# OpenPLCv0_2_0_Power.net
KiCad netlist of a schematic drawn in Altium Designer
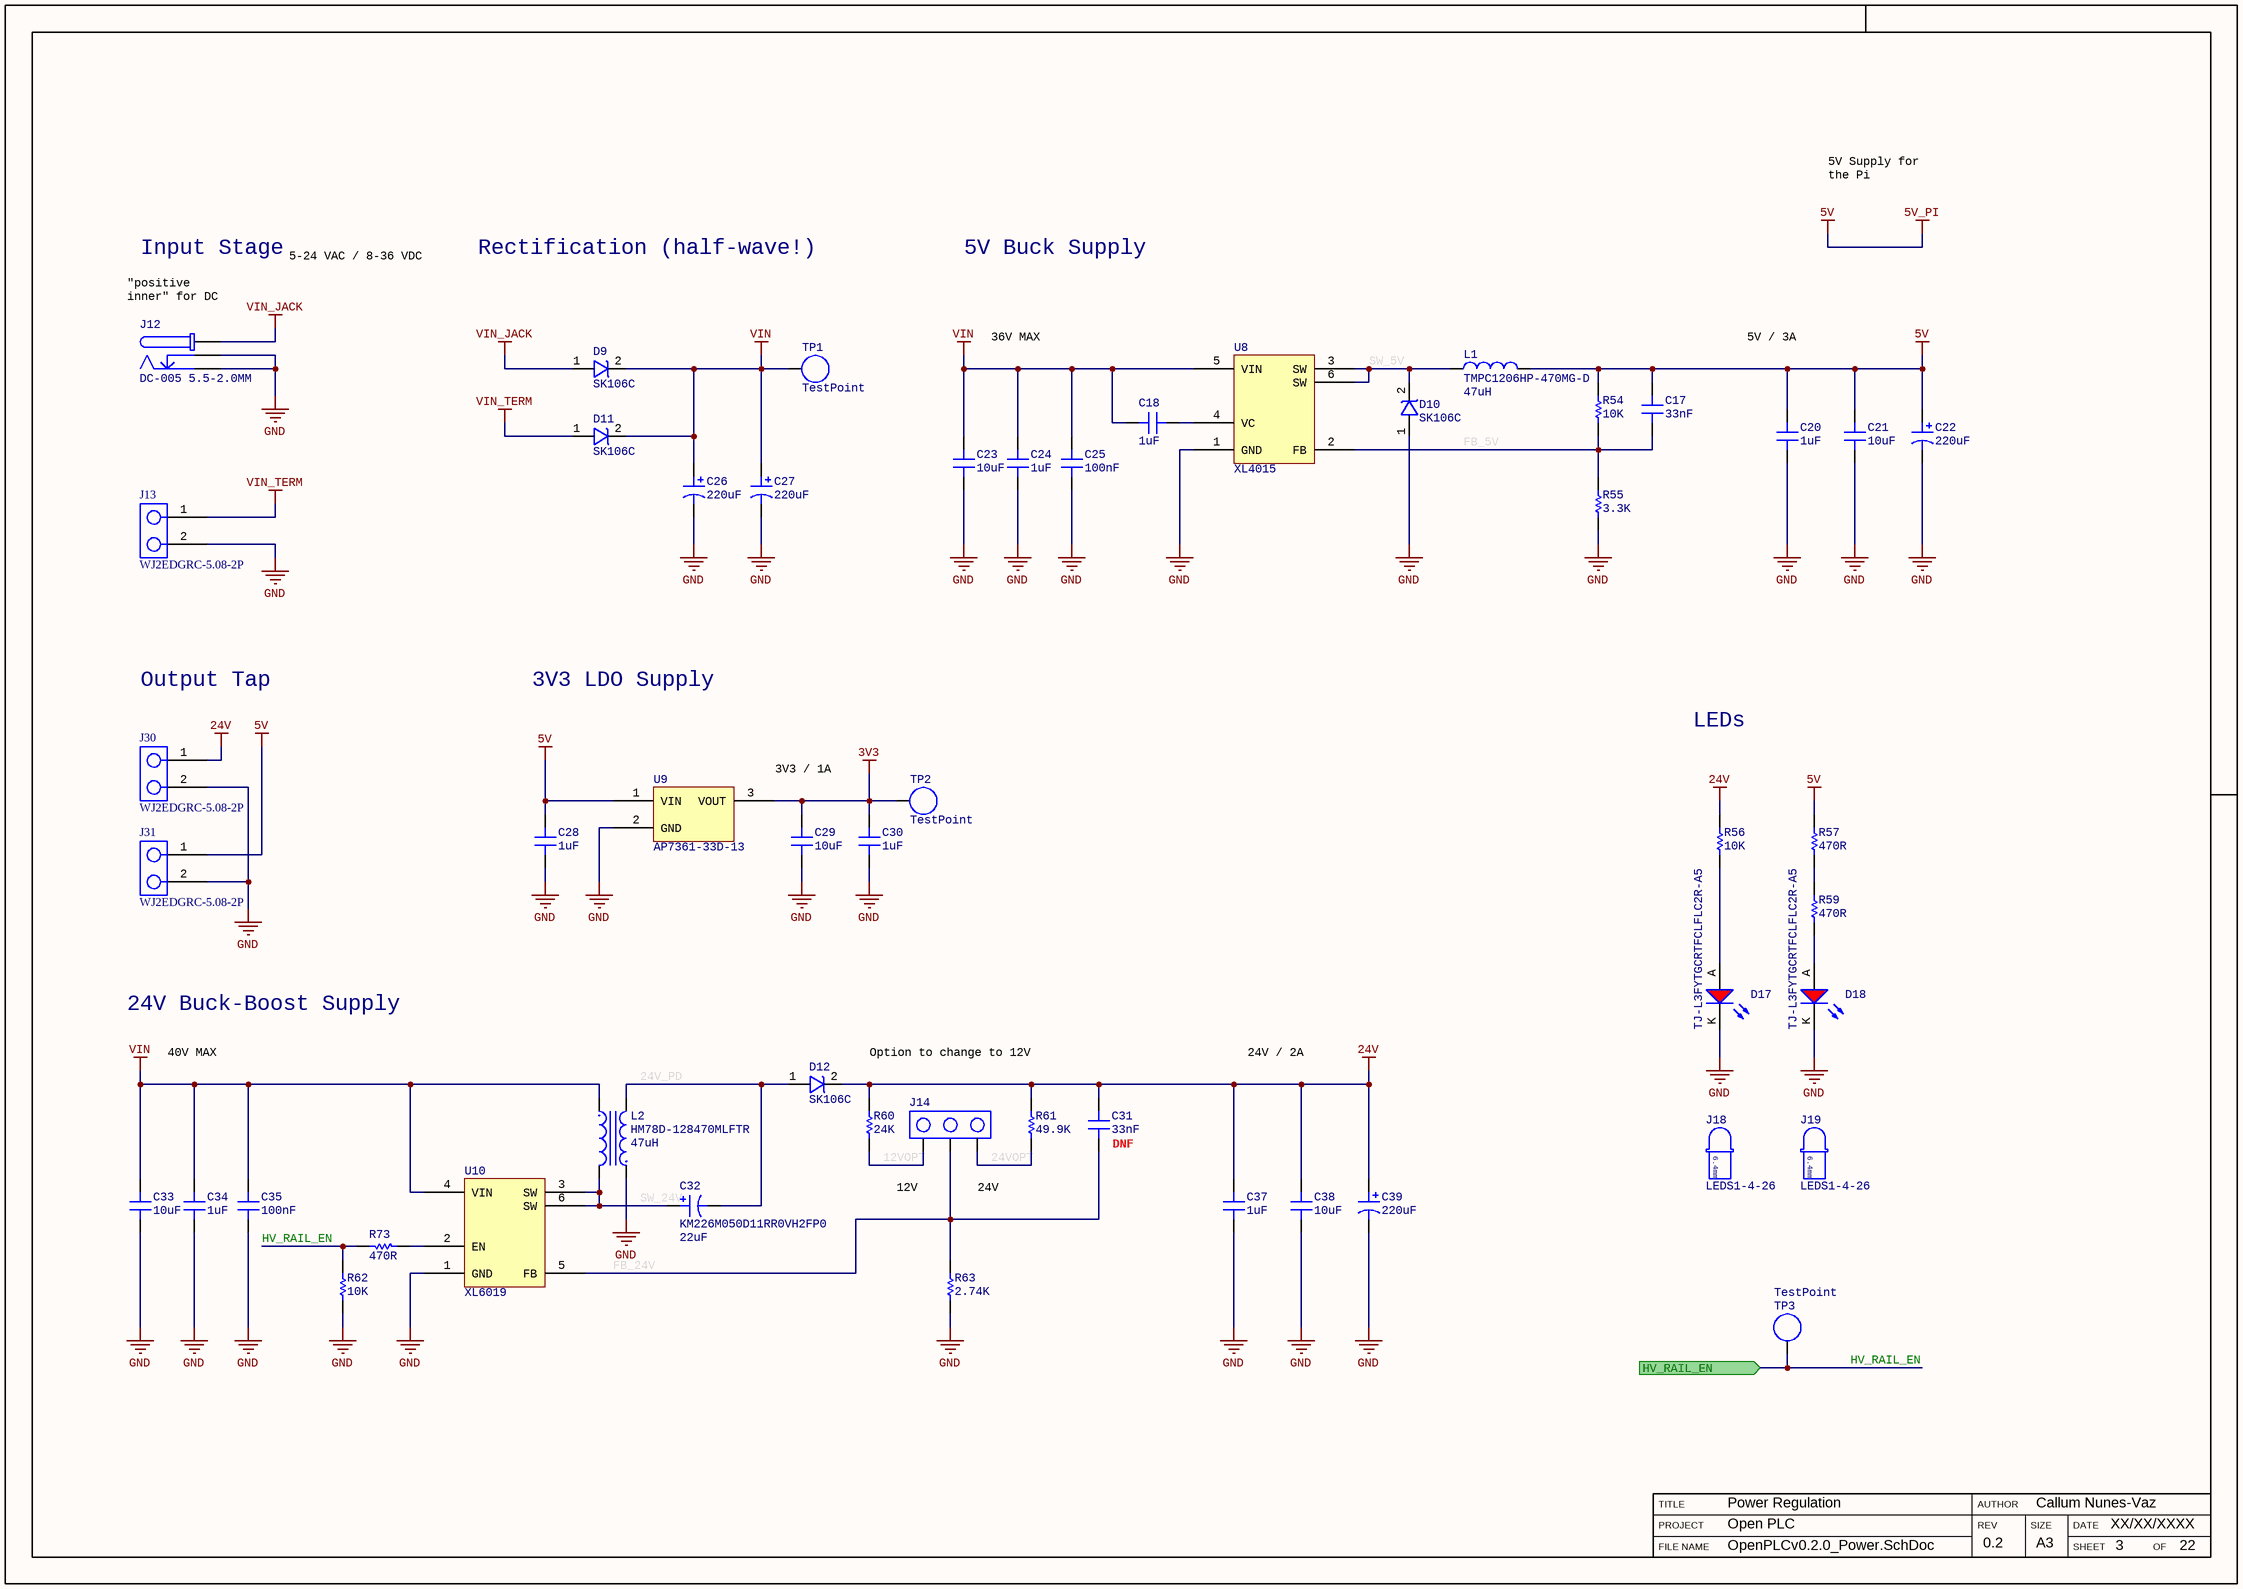
[diagram p0: OpenPLCv0.2.0_Power.SchDoc]

(export (version "E")
  (design (tool "Eeschema 10.0.6"))
  (components
    (comp (ref "C17")
      (value "CC0402KRX7R9BB333")
      (footprint "SMD_CAP_0402(1005)_N")
      (description "33nF ±10% 50V X7R 0402 Multilayer Ceramic Capacitors MLCC - SMD/SMT RoHS")
      (fields (field (name "TOLERANCE") "10%") (field (name "CAPACITANCE") "33nF"))
      (libsource (lib "BrauV2_Capacitor") (part "33nF 0402 50V 10%"))
    )
    (comp (ref "C18")
      (value "CC0603KRX5R9BB105")
      (footprint "SMD_CAP_0603(0201)_N")
      (description "1uF ±10% 50V X5R 0603 Multilayer Ceramic Capacitors MLCC - SMD/SMT RoHS")
      (fields (field (name "TOLERANCE") "10%") (field (name "CAPACITANCE") "1uF"))
      (libsource (lib "BrauV2_Capacitor") (part "1uF 0603 50V 10%"))
    )
    (comp (ref "C20")
      (value "CC0603KRX5R9BB105")
      (footprint "SMD_CAP_0603(0201)_N")
      (description "1uF ±10% 50V X5R 0603 Multilayer Ceramic Capacitors MLCC - SMD/SMT RoHS")
      (fields (field (name "TOLERANCE") "10%") (field (name "CAPACITANCE") "1uF"))
      (libsource (lib "BrauV2_Capacitor") (part "1uF 0603 50V 10%"))
    )
    (comp (ref "C21")
      (value "CC1206KKX5R9BB106")
      (footprint "SMD_CAP_1206(3216)_N")
      (description "10uF ±10% 50V X5R 1206 Multilayer Ceramic Capacitors MLCC - SMD/SMT RoHS")
      (fields (field (name "TOLERANCE") "10%") (field (name "CAPACITANCE") "10uF"))
      (libsource (lib "BrauV2_Capacitor") (part "10uF 1206 50V 10%"))
    )
    (comp (ref "C22")
      (value "ECR1HPT221MLL100012")
      (footprint "Electrolytic_D10mm_H12.5mm")
      (fields (field (name "TOLERANCE") "20%") (field (name "CAPACITANCE") "220uF"))
      (libsource (lib "OpenPLCv0.2.0_Capacitor") (part "ECR1HPT221MLL100012"))
    )
    (comp (ref "C23")
      (value "CC1206KKX5R9BB106")
      (footprint "SMD_CAP_1206(3216)_N")
      (description "10uF ±10% 50V X5R 1206 Multilayer Ceramic Capacitors MLCC - SMD/SMT RoHS")
      (fields (field (name "TOLERANCE") "10%") (field (name "CAPACITANCE") "10uF"))
      (libsource (lib "BrauV2_Capacitor") (part "10uF 1206 50V 10%"))
    )
    (comp (ref "C24")
      (value "CC0603KRX5R9BB105")
      (footprint "SMD_CAP_0603(0201)_N")
      (description "1uF ±10% 50V X5R 0603 Multilayer Ceramic Capacitors MLCC - SMD/SMT RoHS")
      (fields (field (name "TOLERANCE") "10%") (field (name "CAPACITANCE") "1uF"))
      (libsource (lib "BrauV2_Capacitor") (part "1uF 0603 50V 10%"))
    )
    (comp (ref "C25")
      (value "CC0402KRX5R9BB104")
      (footprint "SMD_CAP_0402(1005)_N")
      (description "100nF ±10% 50V X5R 0402 Multilayer Ceramic Capacitors MLCC - SMD/SMT RoHS")
      (fields (field (name "TOLERANCE") "10%") (field (name "CAPACITANCE") "100nF"))
      (libsource (lib "BrauV2_Capacitor") (part "100nF 0402 50V 10%"))
    )
    (comp (ref "C26")
      (value "ECR1HPT221MLL100012")
      (footprint "Electrolytic_D10mm_H12.5mm")
      (fields (field (name "TOLERANCE") "20%") (field (name "CAPACITANCE") "220uF"))
      (libsource (lib "OpenPLCv0.2.0_Capacitor") (part "ECR1HPT221MLL100012"))
    )
    (comp (ref "C27")
      (value "ECR1HPT221MLL100012")
      (footprint "Electrolytic_D10mm_H12.5mm")
      (fields (field (name "TOLERANCE") "20%") (field (name "CAPACITANCE") "220uF"))
      (libsource (lib "OpenPLCv0.2.0_Capacitor") (part "ECR1HPT221MLL100012"))
    )
    (comp (ref "C28")
      (value "CC0603KRX5R9BB105")
      (footprint "SMD_CAP_0603(0201)_N")
      (description "1uF ±10% 50V X5R 0603 Multilayer Ceramic Capacitors MLCC - SMD/SMT RoHS")
      (fields (field (name "TOLERANCE") "10%") (field (name "CAPACITANCE") "1uF"))
      (libsource (lib "BrauV2_Capacitor") (part "1uF 0603 50V 10%"))
    )
    (comp (ref "C29")
      (value "CC1206KKX5R9BB106")
      (footprint "SMD_CAP_1206(3216)_N")
      (description "10uF ±10% 50V X5R 1206 Multilayer Ceramic Capacitors MLCC - SMD/SMT RoHS")
      (fields (field (name "TOLERANCE") "10%") (field (name "CAPACITANCE") "10uF"))
      (libsource (lib "BrauV2_Capacitor") (part "10uF 1206 50V 10%"))
    )
    (comp (ref "C30")
      (value "CC0603KRX5R9BB105")
      (footprint "SMD_CAP_0603(0201)_N")
      (description "1uF ±10% 50V X5R 0603 Multilayer Ceramic Capacitors MLCC - SMD/SMT RoHS")
      (fields (field (name "TOLERANCE") "10%") (field (name "CAPACITANCE") "1uF"))
      (libsource (lib "BrauV2_Capacitor") (part "1uF 0603 50V 10%"))
    )
    (comp (ref "C31")
      (value "CC0402KRX7R9BB333")
      (footprint "SMD_CAP_0402(1005)_N")
      (description "33nF ±10% 50V X7R 0402 Multilayer Ceramic Capacitors MLCC - SMD/SMT RoHS")
      (fields (field (name "TOLERANCE") "10%") (field (name "CAPACITANCE") "33nF"))
      (libsource (lib "BrauV2_Capacitor") (part "33nF 0402 50V 10%"))
    )
    (comp (ref "C32")
      (value "KM226M050D11RR0VH2FP0")
      (footprint "Electrolytic_D5mm_H11mm")
      (fields (field (name "TOLERANCE") "20%") (field (name "CAPACITANCE") "22uF"))
      (libsource (lib "OpenPLCv0.2.0_Capacitor") (part "KM226M050D11RR0VH2FP0"))
    )
    (comp (ref "C33")
      (value "CC1206KKX5R9BB106")
      (footprint "SMD_CAP_1206(3216)_N")
      (description "10uF ±10% 50V X5R 1206 Multilayer Ceramic Capacitors MLCC - SMD/SMT RoHS")
      (fields (field (name "TOLERANCE") "10%") (field (name "CAPACITANCE") "10uF"))
      (libsource (lib "BrauV2_Capacitor") (part "10uF 1206 50V 10%"))
    )
    (comp (ref "C34")
      (value "CC0603KRX5R9BB105")
      (footprint "SMD_CAP_0603(0201)_N")
      (description "1uF ±10% 50V X5R 0603 Multilayer Ceramic Capacitors MLCC - SMD/SMT RoHS")
      (fields (field (name "TOLERANCE") "10%") (field (name "CAPACITANCE") "1uF"))
      (libsource (lib "BrauV2_Capacitor") (part "1uF 0603 50V 10%"))
    )
    (comp (ref "C35")
      (value "CC0402KRX5R9BB104")
      (footprint "SMD_CAP_0402(1005)_N")
      (description "100nF ±10% 50V X5R 0402 Multilayer Ceramic Capacitors MLCC - SMD/SMT RoHS")
      (fields (field (name "TOLERANCE") "10%") (field (name "CAPACITANCE") "100nF"))
      (libsource (lib "BrauV2_Capacitor") (part "100nF 0402 50V 10%"))
    )
    (comp (ref "C37")
      (value "CC0603KRX5R9BB105")
      (footprint "SMD_CAP_0603(0201)_N")
      (description "1uF ±10% 50V X5R 0603 Multilayer Ceramic Capacitors MLCC - SMD/SMT RoHS")
      (fields (field (name "TOLERANCE") "10%") (field (name "CAPACITANCE") "1uF"))
      (libsource (lib "BrauV2_Capacitor") (part "1uF 0603 50V 10%"))
    )
    (comp (ref "C38")
      (value "CC1206KKX5R9BB106")
      (footprint "SMD_CAP_1206(3216)_N")
      (description "10uF ±10% 50V X5R 1206 Multilayer Ceramic Capacitors MLCC - SMD/SMT RoHS")
      (fields (field (name "TOLERANCE") "10%") (field (name "CAPACITANCE") "10uF"))
      (libsource (lib "BrauV2_Capacitor") (part "10uF 1206 50V 10%"))
    )
    (comp (ref "C39")
      (value "ECR1HPT221MLL100012")
      (footprint "Electrolytic_D10mm_H12.5mm")
      (fields (field (name "TOLERANCE") "20%") (field (name "CAPACITANCE") "220uF"))
      (libsource (lib "OpenPLCv0.2.0_Capacitor") (part "ECR1HPT221MLL100012"))
    )
    (comp (ref "D9")
      (value "SK106C")
      (footprint "DO-214AB")
      (description "60V 10A 850mV @ 10A SMC(DO-214AB) Schottky Barrier Diodes (SBD) RoHS")
      (libsource (lib "BrauV2_Diode") (part "SK106C"))
    )
    (comp (ref "D10")
      (value "SK106C")
      (footprint "DO-214AB")
      (description "60V 10A 850mV @ 10A SMC(DO-214AB) Schottky Barrier Diodes (SBD) RoHS")
      (libsource (lib "BrauV2_Diode") (part "SK106C"))
    )
    (comp (ref "D11")
      (value "SK106C")
      (footprint "DO-214AB")
      (description "60V 10A 850mV @ 10A SMC(DO-214AB) Schottky Barrier Diodes (SBD) RoHS")
      (libsource (lib "BrauV2_Diode") (part "SK106C"))
    )
    (comp (ref "D12")
      (value "SK106C")
      (footprint "DO-214AB")
      (description "60V 10A 850mV @ 10A SMC(DO-214AB) Schottky Barrier Diodes (SBD) RoHS")
      (libsource (lib "BrauV2_Diode") (part "SK106C"))
    )
    (comp (ref "D17")
      (value "TJ-L3FYTGCRTFCLFLC2R-A5")
      (footprint "LED_3MM_SPACED_6.4MM_RED")
      (description "LED 3mm Red 620nm~630nm 1.8V~2.6V Through Hole Light Emitting Diodes (LED) RoHS C331031")
      (libsource (lib "BrauV2_Diode") (part "TJ-L3FYTGCRTFCLFLC2R-A5"))
    )
    (comp (ref "D18")
      (value "TJ-L3FYTGCRTFCLFLC2R-A5")
      (footprint "LED_3MM_SPACED_6.4MM_RED")
      (description "LED 3mm Red 620nm~630nm 1.8V~2.6V Through Hole Light Emitting Diodes (LED) RoHS C331031")
      (libsource (lib "BrauV2_Diode") (part "TJ-L3FYTGCRTFCLFLC2R-A5"))
    )
    (comp (ref "J12")
      (value "DC-005 5.5-2.0MM")
      (footprint "DC-005 5.5-2.0MM")
      (description "Through Hole AC/DC Power Plugs & Receptacles RoHS")
      (libsource (lib "BrauV2_Connector") (part "DC-005 5.5-2.0MM"))
    )
    (comp (ref "J13")
      (value "WJ2EDGRC-5.08-2P")
      (footprint "796638-2_BoardEdgeAlt")
      (description "Covered（4Sided） 2 1 0.200\"（5.08mm） 2 P=5.08mm Pluggable System Terminal Block RoHS")
      (libsource (lib "OpenPLCv0.2.0_Connector") (part "WJ2EDGRC-5.08-2P"))
    )
    (comp (ref "J14")
      (value "12251103CNG0S115001")
      (footprint "Header_3POS")
      (description "Pin Header 3 1 right-angle，180degrees 2.54mm Through Hole,P=2.54mm Pin Header & Female Header RoHS")
      (libsource (lib "BrauV2_Connector") (part "3-way Jumper"))
    )
    (comp (ref "J18")
      (value "LEDS1-4-26")
      (footprint "3MM_LED_SPACER_6.4MM")
      (description "3mm LED spacer 6.4mm height")
      (libsource (lib "BrauV2_Misc") (part "LEDS1-4-26"))
    )
    (comp (ref "J19")
      (value "LEDS1-4-26")
      (footprint "3MM_LED_SPACER_6.4MM")
      (description "3mm LED spacer 6.4mm height")
      (libsource (lib "BrauV2_Misc") (part "LEDS1-4-26"))
    )
    (comp (ref "J30")
      (value "WJ2EDGRC-5.08-2P")
      (footprint "796638-2_BoardEdgeAlt")
      (description "Covered（4Sided） 2 1 0.200\"（5.08mm） 2 P=5.08mm Pluggable System Terminal Block RoHS")
      (libsource (lib "OpenPLCv0.2.0_Connector") (part "WJ2EDGRC-5.08-2P"))
    )
    (comp (ref "J31")
      (value "WJ2EDGRC-5.08-2P")
      (footprint "796638-2_BoardEdgeAlt")
      (description "Covered（4Sided） 2 1 0.200\"（5.08mm） 2 P=5.08mm Pluggable System Terminal Block RoHS")
      (libsource (lib "OpenPLCv0.2.0_Connector") (part "WJ2EDGRC-5.08-2P"))
    )
    (comp (ref "L1")
      (value "TMPC1206HP-470MG-D")
      (footprint "TMPC1206HP-470MG-D")
      (description "47uH ±20% 5.5A 80mΩ SMD,13.5x12.5x5.7mm Power Inductors RoHS")
      (fields (field (name "INDUCTANCE") "47uH"))
      (libsource (lib "BrauV2_Inductor") (part "TMPC1206HP-470MG-D"))
    )
    (comp (ref "L2")
      (value "HM78D-128470MLFTR")
      (footprint "HM78D-128470MLFTR")
      (description "Coupled Inductors 47uH 20%")
      (fields (field (name "PARALLEL INDUCTANCE") "47uH"))
      (libsource (lib "BrauV2_Inductor") (part "HM78D-128470MLFTR"))
    )
    (comp (ref "R54")
      (value "RC0402FR-0710KL")
      (footprint "SMD_RES_0402(1005)_N")
      (description "10kΩ ±1% 1/16W ±100ppm/℃ 0402 Chip Resistor - Surface Mount RoHS")
      (fields (field (name "TOLERANCE") "1%") (field (name "RESISTANCE") "10K"))
      (libsource (lib "BrauV2_Resistor") (part "10K 0402 1% 1/16W"))
    )
    (comp (ref "R55")
      (value "RC0402FR-073K3L")
      (footprint "SMD_RES_0402(1005)_N")
      (description "3.3kΩ ±1% 1/16W ±100ppm/℃ 0402 Chip Resistor - Surface Mount RoHS")
      (fields (field (name "TOLERANCE") "1%") (field (name "RESISTANCE") "3.3K"))
      (libsource (lib "BrauV2_Resistor") (part "3K3 0402 1% 1/16W"))
    )
    (comp (ref "R56")
      (value "RC0402FR-0710KL")
      (footprint "SMD_RES_0402(1005)_N")
      (description "10kΩ ±1% 1/16W ±100ppm/℃ 0402 Chip Resistor - Surface Mount RoHS")
      (fields (field (name "TOLERANCE") "1%") (field (name "RESISTANCE") "10K"))
      (libsource (lib "BrauV2_Resistor") (part "10K 0402 1% 1/16W"))
    )
    (comp (ref "R57")
      (value "RC0402FR-07470RL")
      (footprint "SMD_RES_0402(1005)_N")
      (description "470Ω ±1% 1/16W ±100ppm/℃ 0402 Chip Resistor - Surface Mount RoHS")
      (fields (field (name "TOLERANCE") "1%") (field (name "RESISTANCE") "470R"))
      (libsource (lib "BrauV2_Resistor") (part "470R 0402 1% 1W"))
    )
    (comp (ref "R59")
      (value "RC0402FR-07470RL")
      (footprint "SMD_RES_0402(1005)_N")
      (description "470Ω ±1% 1/16W ±100ppm/℃ 0402 Chip Resistor - Surface Mount RoHS")
      (fields (field (name "TOLERANCE") "1%") (field (name "RESISTANCE") "470R"))
      (libsource (lib "BrauV2_Resistor") (part "470R 0402 1% 1W"))
    )
    (comp (ref "R60")
      (value "RC0402FR-0724KL")
      (footprint "SMD_RES_0402(1005)_N")
      (description "24kΩ ±1% 1/16W ±100ppm/℃ 0402 Chip Resistor - Surface Mount RoHS")
      (fields (field (name "TOLERANCE") "1%") (field (name "RESISTANCE") "24K"))
      (libsource (lib "BrauV2_Resistor") (part "24K 0402 1% 1/16W"))
    )
    (comp (ref "R61")
      (value "RC0402FR-0749K9L")
      (footprint "SMD_RES_0402(1005)_N")
      (description "49.9kΩ ±1% 1/16W ±100ppm/℃ 0402 Chip Resistor - Surface Mount RoHS")
      (fields (field (name "TOLERANCE") "1%") (field (name "RESISTANCE") "49.9K"))
      (libsource (lib "BrauV2_Resistor") (part "49K9 0402 1% 1/16W"))
    )
    (comp (ref "R62")
      (value "RC0402FR-0710KL")
      (footprint "SMD_RES_0402(1005)_N")
      (description "10kΩ ±1% 1/16W ±100ppm/℃ 0402 Chip Resistor - Surface Mount RoHS")
      (fields (field (name "TOLERANCE") "1%") (field (name "RESISTANCE") "10K"))
      (libsource (lib "BrauV2_Resistor") (part "10K 0402 1% 1/16W"))
    )
    (comp (ref "R63")
      (value "RC0402FR-072K74L")
      (footprint "SMD_RES_0402(1005)_N")
      (description "2.74kΩ ±1% 1/16W ±100ppm/℃ 0402 Chip Resistor - Surface Mount RoHS")
      (fields (field (name "TOLERANCE") "1%") (field (name "RESISTANCE") "2.74K"))
      (libsource (lib "BrauV2_Resistor") (part "2K74 0402 1% 1/16W"))
    )
    (comp (ref "R73")
      (value "RC0402FR-07470RL")
      (footprint "SMD_RES_0402(1005)_N")
      (description "470Ω ±1% 1/16W ±100ppm/℃ 0402 Chip Resistor - Surface Mount RoHS")
      (fields (field (name "TOLERANCE") "1%") (field (name "RESISTANCE") "470R"))
      (libsource (lib "BrauV2_Resistor") (part "470R 0402 1% 1W"))
    )
    (comp (ref "TP1")
      (value "TestPoint")
      (footprint "Pad")
      (libsource (lib "OpenPLCv0.2.0_Misc") (part "Test point"))
    )
    (comp (ref "TP2")
      (value "TestPoint")
      (footprint "Pad")
      (libsource (lib "OpenPLCv0.2.0_Misc") (part "Test point"))
    )
    (comp (ref "TP3")
      (value "TestPoint")
      (footprint "Pad")
      (libsource (lib "OpenPLCv0.2.0_Misc") (part "Test point"))
    )
    (comp (ref "U8")
      (value "XL4015")
      (footprint "TO-263-5")
      (description "XLSEMI 5A 180KHz 36V Buck DC to DC Converter")
      (libsource (lib "BrauV2_IC") (part "XL4015"))
    )
    (comp (ref "U9")
      (value "AP7361-33D-13")
      (footprint "TO-252")
      (description "Fixed 6V 3.3V 700mV @ 1A TO-252 Dropout Regulators(LDO) RoHS")
      (libsource (lib "BrauV2_IC") (part "AP7361-33D-13"))
    )
    (comp (ref "U10")
      (value "XL6019")
      (footprint "TO-263-5")
      (description "XLSEMI 180KHz 60V 5A Switching Current Boost / Buck-Boost / Inverting DC/DC Converter")
      (libsource (lib "BrauV2_IC") (part "XL6019"))
    )
  )
  (nets
    (net (code "1") (name "/12VOPT") (class "Default")
      (node (ref "J14") (pin "1") (pinfunction "1_1") (pintype "passive"))
      (node (ref "R60") (pin "1") (pinfunction "1_1") (pintype "passive"))
    )
    (net (code "2") (name "/24VOPT") (class "Default")
      (node (ref "J14") (pin "3") (pinfunction "3_3") (pintype "passive"))
      (node (ref "R61") (pin "1") (pinfunction "1_1") (pintype "passive"))
    )
    (net (code "3") (name "/24V_PD") (class "Default")
      (node (ref "C32") (pin "2") (pinfunction "2_2") (pintype "passive"))
      (node (ref "D12") (pin "1") (pinfunction "ANODE_1") (pintype "passive"))
      (node (ref "L2") (pin "3") (pinfunction "3_3") (pintype "passive"))
    )
    (net (code "4") (name "/FB_5V") (class "Default")
      (node (ref "C17") (pin "1") (pinfunction "1_1") (pintype "passive"))
      (node (ref "R54") (pin "1") (pinfunction "1_1") (pintype "passive"))
      (node (ref "R55") (pin "2") (pinfunction "2_2") (pintype "passive"))
      (node (ref "U8") (pin "2") (pinfunction "FB_2") (pintype "passive"))
    )
    (net (code "5") (name "/FB_24V") (class "Default")
      (node (ref "C31") (pin "1") (pinfunction "1_1") (pintype "passive"))
      (node (ref "J14") (pin "2") (pinfunction "2_2") (pintype "passive"))
      (node (ref "R63") (pin "2") (pinfunction "2_2") (pintype "passive"))
      (node (ref "U10") (pin "5") (pinfunction "FB_5") (pintype "passive"))
    )
    (net (code "6") (name "/HV_RAIL_EN") (class "Default")
      (node (ref "R62") (pin "2") (pinfunction "2_2") (pintype "passive"))
      (node (ref "R73") (pin "1") (pinfunction "1_1") (pintype "passive"))
      (node (ref "TP3") (pin "1") (pinfunction "1_1") (pintype "passive"))
    )
    (net (code "7") (name "/SW_5V") (class "Default")
      (node (ref "D10") (pin "2") (pinfunction "CATHODE_2") (pintype "passive"))
      (node (ref "L1") (pin "1") (pinfunction "1_1") (pintype "passive"))
      (node (ref "U8") (pin "3") (pinfunction "SW_3") (pintype "passive"))
      (node (ref "U8") (pin "6") (pinfunction "SW_6") (pintype "passive"))
    )
    (net (code "8") (name "/SW_24V") (class "Default")
      (node (ref "C32") (pin "1") (pinfunction "1_1") (pintype "passive"))
      (node (ref "L2") (pin "4") (pinfunction "4_4") (pintype "passive"))
      (node (ref "U10") (pin "3") (pinfunction "SW_3") (pintype "passive"))
      (node (ref "U10") (pin "6") (pinfunction "SW_6") (pintype "passive"))
    )
    (net (code "9") (name "3V3") (class "Default")
      (node (ref "C29") (pin "2") (pinfunction "2_2") (pintype "passive"))
      (node (ref "C30") (pin "2") (pinfunction "2_2") (pintype "passive"))
      (node (ref "TP2") (pin "1") (pinfunction "1_1") (pintype "passive"))
      (node (ref "U9") (pin "3") (pinfunction "VOUT_3") (pintype "passive"))
    )
    (net (code "10") (name "5V") (class "Default")
      (node (ref "C17") (pin "2") (pinfunction "2_2") (pintype "passive"))
      (node (ref "C20") (pin "2") (pinfunction "2_2") (pintype "passive"))
      (node (ref "C21") (pin "2") (pinfunction "2_2") (pintype "passive"))
      (node (ref "C22") (pin "1") (pinfunction "1_1") (pintype "passive"))
      (node (ref "C28") (pin "2") (pinfunction "2_2") (pintype "passive"))
      (node (ref "J31") (pin "1") (pinfunction "1_1") (pintype "passive"))
      (node (ref "L1") (pin "2") (pinfunction "2_2") (pintype "passive"))
      (node (ref "R54") (pin "2") (pinfunction "2_2") (pintype "passive"))
      (node (ref "R57") (pin "2") (pinfunction "2_2") (pintype "passive"))
      (node (ref "U9") (pin "1") (pinfunction "VIN_1") (pintype "passive"))
    )
    (net (code "11") (name "24V") (class "Default")
      (node (ref "C31") (pin "2") (pinfunction "2_2") (pintype "passive"))
      (node (ref "C37") (pin "2") (pinfunction "2_2") (pintype "passive"))
      (node (ref "C38") (pin "2") (pinfunction "2_2") (pintype "passive"))
      (node (ref "C39") (pin "1") (pinfunction "1_1") (pintype "passive"))
      (node (ref "D12") (pin "2") (pinfunction "CATHODE_2") (pintype "passive"))
      (node (ref "J30") (pin "1") (pinfunction "1_1") (pintype "passive"))
      (node (ref "R56") (pin "2") (pinfunction "2_2") (pintype "passive"))
      (node (ref "R60") (pin "2") (pinfunction "2_2") (pintype "passive"))
      (node (ref "R61") (pin "2") (pinfunction "2_2") (pintype "passive"))
    )
    (net (code "12") (name "GND") (class "Default")
      (node (ref "C20") (pin "1") (pinfunction "1_1") (pintype "passive"))
      (node (ref "C21") (pin "1") (pinfunction "1_1") (pintype "passive"))
      (node (ref "C22") (pin "2") (pinfunction "2_2") (pintype "passive"))
      (node (ref "C23") (pin "1") (pinfunction "1_1") (pintype "passive"))
      (node (ref "C24") (pin "1") (pinfunction "1_1") (pintype "passive"))
      (node (ref "C25") (pin "1") (pinfunction "1_1") (pintype "passive"))
      (node (ref "C26") (pin "2") (pinfunction "2_2") (pintype "passive"))
      (node (ref "C27") (pin "2") (pinfunction "2_2") (pintype "passive"))
      (node (ref "C28") (pin "1") (pinfunction "1_1") (pintype "passive"))
      (node (ref "C29") (pin "1") (pinfunction "1_1") (pintype "passive"))
      (node (ref "C30") (pin "1") (pinfunction "1_1") (pintype "passive"))
      (node (ref "C33") (pin "1") (pinfunction "1_1") (pintype "passive"))
      (node (ref "C34") (pin "1") (pinfunction "1_1") (pintype "passive"))
      (node (ref "C35") (pin "1") (pinfunction "1_1") (pintype "passive"))
      (node (ref "C37") (pin "1") (pinfunction "1_1") (pintype "passive"))
      (node (ref "C38") (pin "1") (pinfunction "1_1") (pintype "passive"))
      (node (ref "C39") (pin "2") (pinfunction "2_2") (pintype "passive"))
      (node (ref "D10") (pin "1") (pinfunction "ANODE_1") (pintype "passive"))
      (node (ref "D17") (pin "K") (pinfunction "K_K") (pintype "passive"))
      (node (ref "D18") (pin "K") (pinfunction "K_K") (pintype "passive"))
      (node (ref "J12") (pin "2") (pinfunction "2_2") (pintype "passive"))
      (node (ref "J12") (pin "3") (pinfunction "3_3") (pintype "passive"))
      (node (ref "J13") (pin "2") (pinfunction "2_2") (pintype "passive"))
      (node (ref "J30") (pin "2") (pinfunction "2_2") (pintype "passive"))
      (node (ref "J31") (pin "2") (pinfunction "2_2") (pintype "passive"))
      (node (ref "L2") (pin "1") (pinfunction "1_1") (pintype "passive"))
      (node (ref "R55") (pin "1") (pinfunction "1_1") (pintype "passive"))
      (node (ref "R62") (pin "1") (pinfunction "1_1") (pintype "passive"))
      (node (ref "R63") (pin "1") (pinfunction "1_1") (pintype "passive"))
      (node (ref "U10") (pin "1") (pinfunction "GND_1") (pintype "passive"))
      (node (ref "U8") (pin "1") (pinfunction "GND_1") (pintype "passive"))
      (node (ref "U9") (pin "2") (pinfunction "GND_2") (pintype "passive"))
    )
    (net (code "13") (name "Net-(D17-PadA)") (class "Default")
      (node (ref "D17") (pin "A") (pinfunction "A_A") (pintype "passive"))
      (node (ref "R56") (pin "1") (pinfunction "1_1") (pintype "passive"))
    )
    (net (code "14") (name "Net-(D18-PadA)") (class "Default")
      (node (ref "D18") (pin "A") (pinfunction "A_A") (pintype "passive"))
      (node (ref "R59") (pin "1") (pinfunction "1_1") (pintype "passive"))
    )
    (net (code "15") (name "Net-(R57-Pad1)") (class "Default")
      (node (ref "R57") (pin "1") (pinfunction "1_1") (pintype "passive"))
      (node (ref "R59") (pin "2") (pinfunction "2_2") (pintype "passive"))
    )
    (net (code "16") (name "Net-(U8-VC)") (class "Default")
      (node (ref "C18") (pin "1") (pinfunction "1_1") (pintype "passive"))
      (node (ref "U8") (pin "4") (pinfunction "VC_4") (pintype "passive"))
    )
    (net (code "17") (name "Net-(U10-EN)") (class "Default")
      (node (ref "R73") (pin "2") (pinfunction "2_2") (pintype "passive"))
      (node (ref "U10") (pin "2") (pinfunction "EN_2") (pintype "passive"))
    )
    (net (code "18") (name "VIN") (class "Default")
      (node (ref "C18") (pin "2") (pinfunction "2_2") (pintype "passive"))
      (node (ref "C23") (pin "2") (pinfunction "2_2") (pintype "passive"))
      (node (ref "C24") (pin "2") (pinfunction "2_2") (pintype "passive"))
      (node (ref "C25") (pin "2") (pinfunction "2_2") (pintype "passive"))
      (node (ref "C26") (pin "1") (pinfunction "1_1") (pintype "passive"))
      (node (ref "C27") (pin "1") (pinfunction "1_1") (pintype "passive"))
      (node (ref "C33") (pin "2") (pinfunction "2_2") (pintype "passive"))
      (node (ref "C34") (pin "2") (pinfunction "2_2") (pintype "passive"))
      (node (ref "C35") (pin "2") (pinfunction "2_2") (pintype "passive"))
      (node (ref "D11") (pin "2") (pinfunction "CATHODE_2") (pintype "passive"))
      (node (ref "D9") (pin "2") (pinfunction "CATHODE_2") (pintype "passive"))
      (node (ref "L2") (pin "2") (pinfunction "2_2") (pintype "passive"))
      (node (ref "TP1") (pin "1") (pinfunction "1_1") (pintype "passive"))
      (node (ref "U10") (pin "4") (pinfunction "VIN_4") (pintype "passive"))
      (node (ref "U8") (pin "5") (pinfunction "VIN_5") (pintype "passive"))
    )
    (net (code "19") (name "VIN_JACK") (class "Default")
      (node (ref "D9") (pin "1") (pinfunction "ANODE_1") (pintype "passive"))
      (node (ref "J12") (pin "4") (pinfunction "4_4") (pintype "passive"))
    )
    (net (code "20") (name "VIN_TERM") (class "Default")
      (node (ref "D11") (pin "1") (pinfunction "ANODE_1") (pintype "passive"))
      (node (ref "J13") (pin "1") (pinfunction "1_1") (pintype "passive"))
    )
  )
)
